# design.net
KiCad netlist of a schematic drawn in Altium Designer
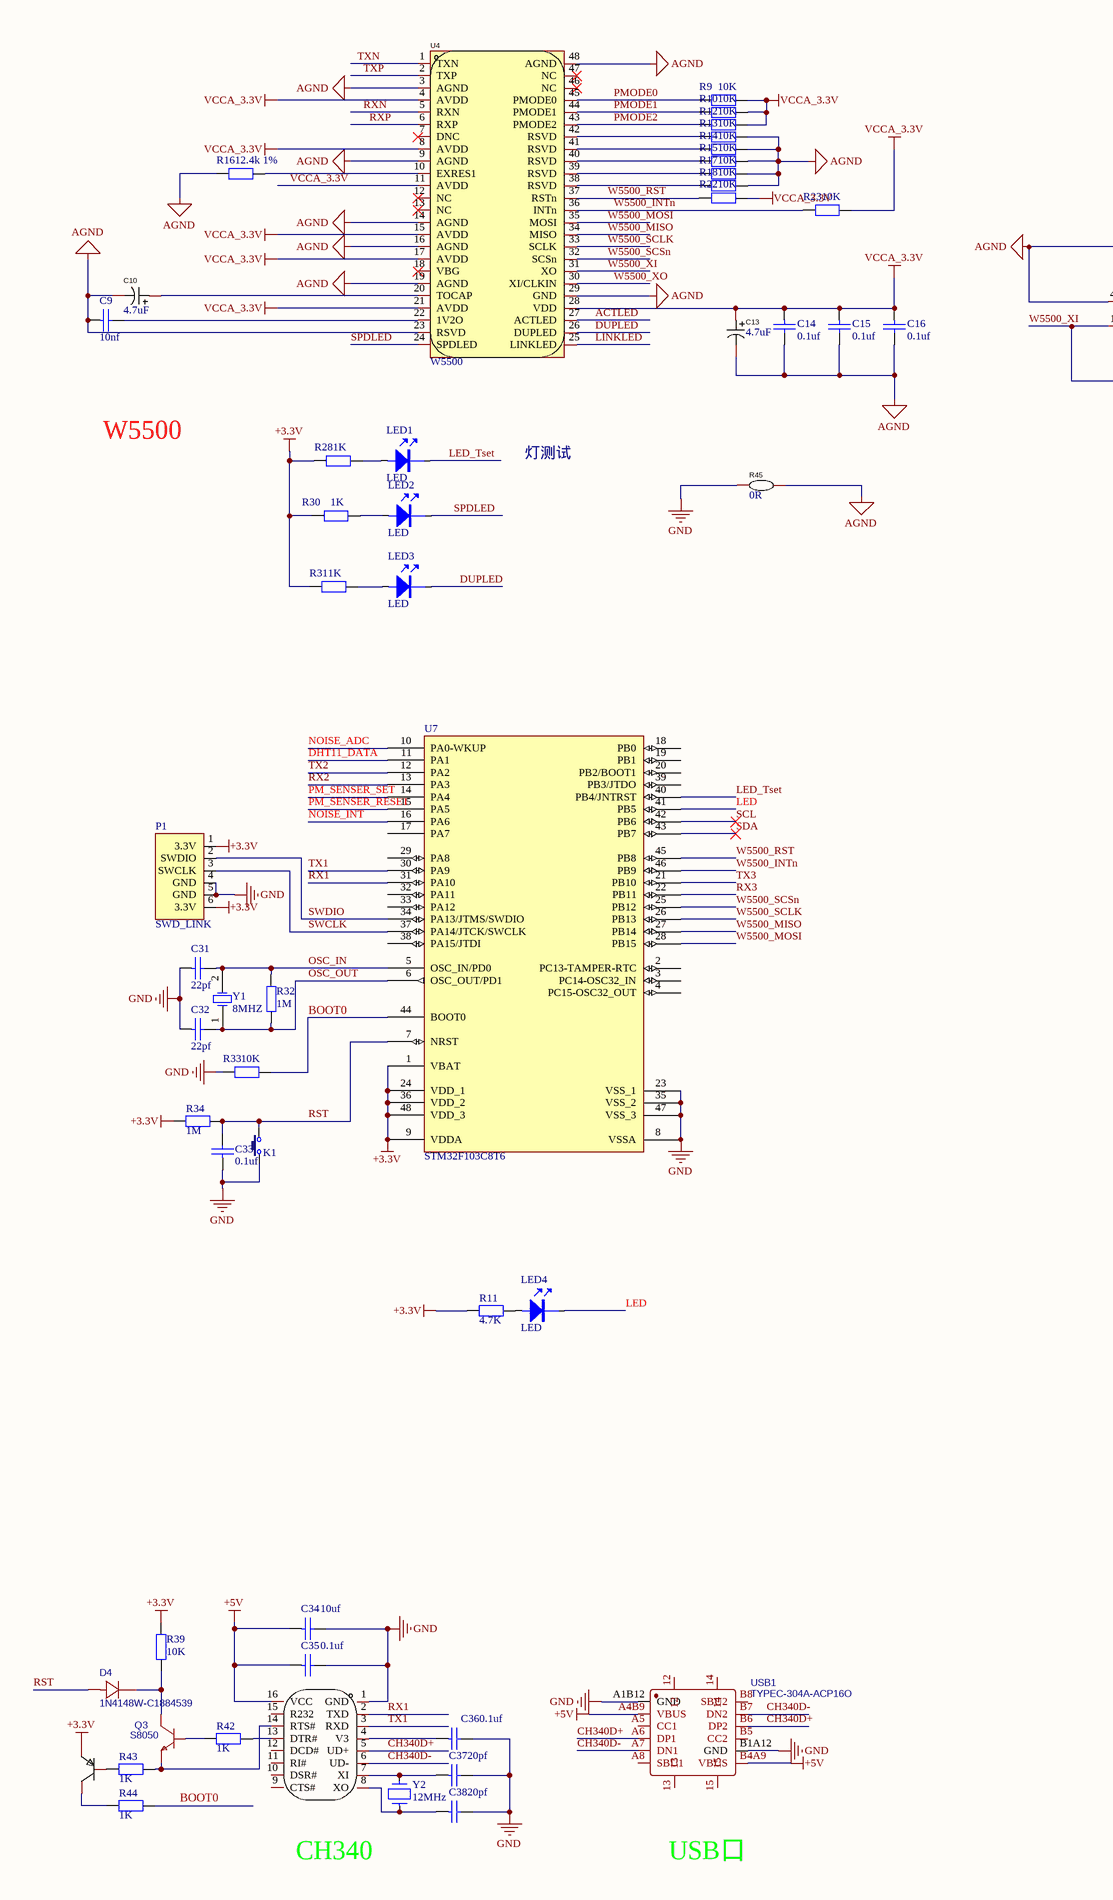
[diagram p0: 气象传感器.SchDoc, left]
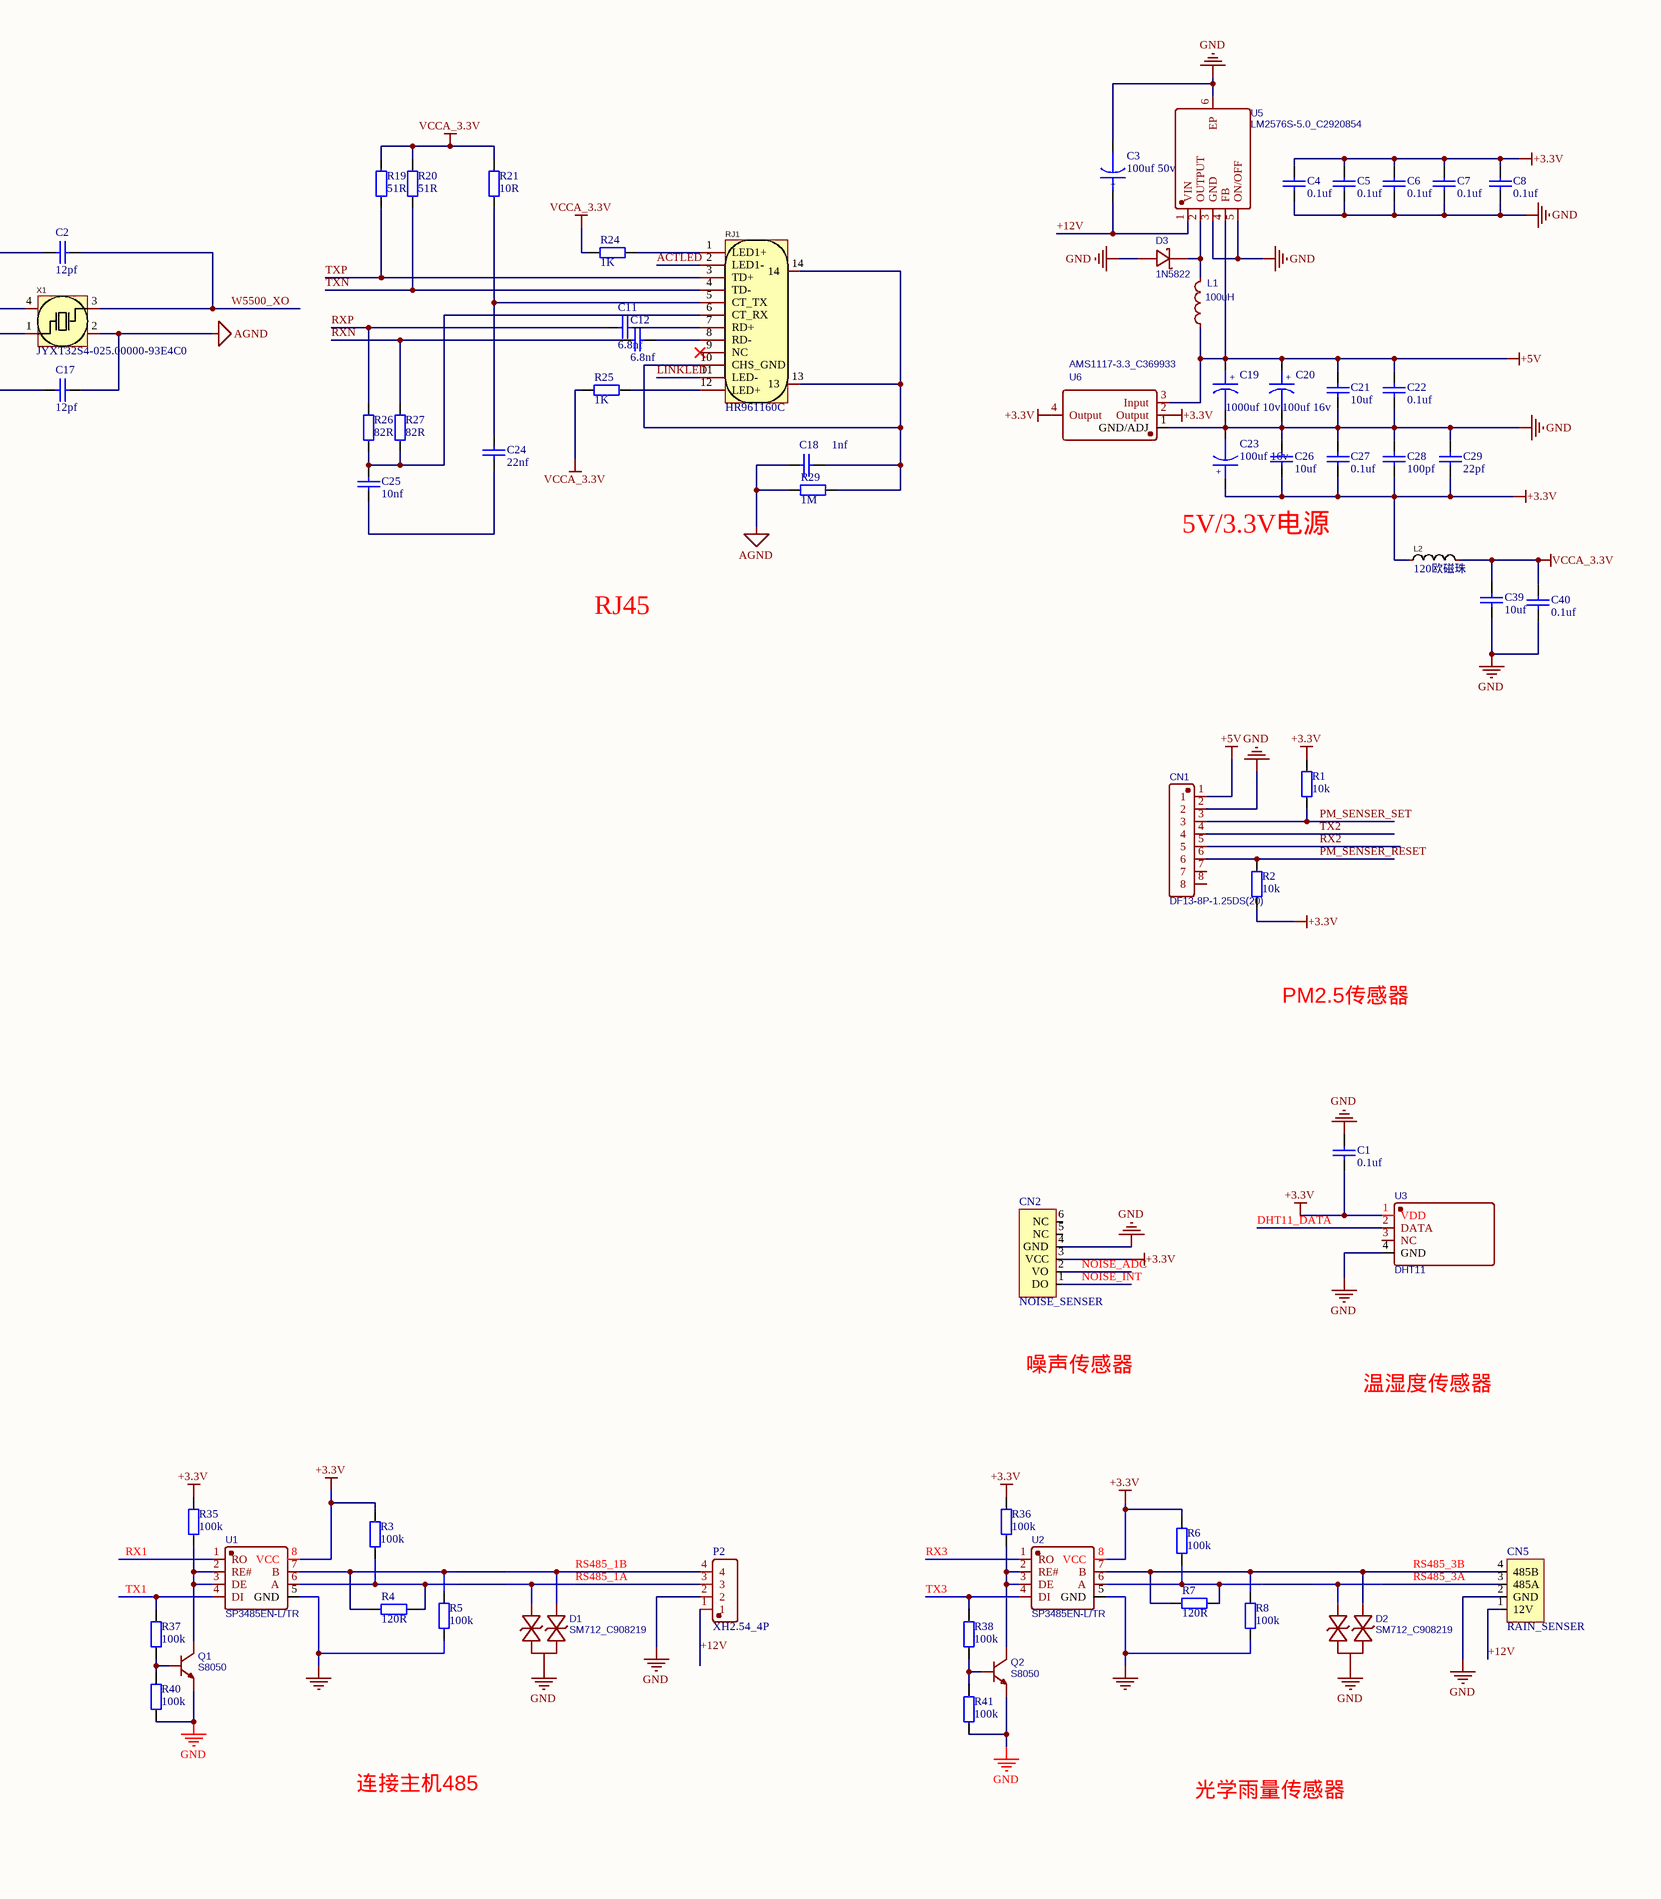
[diagram p1: 气象传感器.SchDoc, right]

(export (version "E")
  (design (tool "Eeschema 10.0.6"))
  (components
    (comp (ref "C1")
      (value "0.1uf")
      (footprint "0603C")
      (description "Capacitor")
      (libsource (lib "单灯控制器nanosim") (part "CAP"))
    )
    (comp (ref "C2")
      (value "12pf")
      (footprint "0603C")
      (description "Capacitor")
      (libsource (lib "GFZJ 主控制板") (part "CAP"))
    )
    (comp (ref "C3")
      (value "100uf 50v")
      (footprint "CAP-TH_BD8.0-P3.50-D0.6-FD")
      (description "Capacitor")
      (libsource (lib "GFZJ 主控制板") (part "CAP+"))
    )
    (comp (ref "C4")
      (value "0.1uf")
      (footprint "0603C")
      (description "Capacitor")
      (libsource (lib "GFZJ 主控制板") (part "CAP"))
    )
    (comp (ref "C5")
      (value "0.1uf")
      (footprint "0603C")
      (description "Capacitor")
      (libsource (lib "GFZJ 主控制板") (part "CAP"))
    )
    (comp (ref "C6")
      (value "0.1uf")
      (footprint "0603C")
      (description "Capacitor")
      (libsource (lib "GFZJ 主控制板") (part "CAP"))
    )
    (comp (ref "C7")
      (value "0.1uf")
      (footprint "0603C")
      (description "Capacitor")
      (libsource (lib "GFZJ 主控制板") (part "CAP"))
    )
    (comp (ref "C8")
      (value "0.1uf")
      (footprint "0603C")
      (description "Capacitor")
      (libsource (lib "GFZJ 主控制板") (part "CAP"))
    )
    (comp (ref "C9")
      (value "10nf")
      (footprint "0603C")
      (description "Capacitor")
      (libsource (lib "GFZJ 主控制板") (part "CAP"))
    )
    (comp (ref "C10")
      (value "4.7uF")
      (footprint "CAP-SMD_L1.6-W0.9-FD")
      (description "钽电容")
      (fields (field (name "MANUFACTURER") "Kyocera AVX") (field (name "MANUFACTURER PART") "F980J106MMA"))
      (libsource (lib "Modbus") (part "F980J106MMA"))
    )
    (comp (ref "C11")
      (value "6.8nf")
      (footprint "0603C")
      (description "Capacitor")
      (libsource (lib "GFZJ 主控制板") (part "CAP"))
    )
    (comp (ref "C12")
      (value "6.8nf")
      (footprint "0603C")
      (description "Capacitor")
      (libsource (lib "GFZJ 主控制板") (part "CAP"))
    )
    (comp (ref "C13")
      (value "4.7uF")
      (footprint "CAP-SMD_L1.6-W0.9-FD")
      (description "钽电容")
      (fields (field (name "MANUFACTURER") "Kyocera AVX") (field (name "MANUFACTURER PART") "F980J106MMA"))
      (libsource (lib "Modbus") (part "F980J106MMA"))
    )
    (comp (ref "C14")
      (value "0.1uf")
      (footprint "0603C")
      (description "Capacitor")
      (libsource (lib "GFZJ 主控制板") (part "CAP"))
    )
    (comp (ref "C15")
      (value "0.1uf")
      (footprint "0603C")
      (description "Capacitor")
      (libsource (lib "GFZJ 主控制板") (part "CAP"))
    )
    (comp (ref "C16")
      (value "0.1uf")
      (footprint "0603C")
      (description "Capacitor")
      (libsource (lib "GFZJ 主控制板") (part "CAP"))
    )
    (comp (ref "C17")
      (value "12pf")
      (footprint "0603C")
      (description "Capacitor")
      (libsource (lib "GFZJ 主控制板") (part "CAP"))
    )
    (comp (ref "C18")
      (value "1nf")
      (footprint "0603C")
      (description "Capacitor")
      (libsource (lib "GFZJ 主控制板") (part "CAP"))
    )
    (comp (ref "C19")
      (value "1000uf 10v")
      (footprint "CAP-TH_BD8.0-P3.50-D0.6-FD")
      (description "Capacitor")
      (libsource (lib "") (part "CAP+_1"))
    )
    (comp (ref "C20")
      (value "100uf 16v")
      (footprint "CAP-TH_BD5.0-P2.00-D0.8-FD")
      (description "Capacitor")
      (libsource (lib "") (part "CAP+_1"))
    )
    (comp (ref "C21")
      (value "10uf")
      (footprint "0805C")
      (description "Capacitor")
      (libsource (lib "GFZJ 主控制板") (part "CAP"))
    )
    (comp (ref "C22")
      (value "0.1uf")
      (footprint "0603C")
      (description "Capacitor")
      (libsource (lib "GFZJ 主控制板") (part "CAP"))
    )
    (comp (ref "C23")
      (value "100uf 16v")
      (footprint "CAP-TH_BD5.0-P2.00-D0.8-FD")
      (description "Capacitor")
      (libsource (lib "") (part "CAP+_1"))
    )
    (comp (ref "C24")
      (value "22nf")
      (footprint "0603C")
      (description "Capacitor")
      (libsource (lib "GFZJ 主控制板") (part "CAP"))
    )
    (comp (ref "C25")
      (value "10nf")
      (footprint "0603C")
      (description "Capacitor")
      (libsource (lib "GFZJ 主控制板") (part "CAP"))
    )
    (comp (ref "C26")
      (value "10uf")
      (footprint "0805C")
      (description "Capacitor")
      (libsource (lib "GFZJ 主控制板") (part "CAP"))
    )
    (comp (ref "C27")
      (value "0.1uf")
      (footprint "0603C")
      (description "Capacitor")
      (libsource (lib "GFZJ 主控制板") (part "CAP"))
    )
    (comp (ref "C28")
      (value "100pf")
      (footprint "0603C")
      (description "Capacitor")
      (libsource (lib "GFZJ 主控制板") (part "CAP"))
    )
    (comp (ref "C29")
      (value "22pf")
      (footprint "0603C")
      (description "Capacitor")
      (libsource (lib "GFZJ 主控制板") (part "CAP"))
    )
    (comp (ref "C31")
      (value "22pf")
      (footprint "0603C")
      (description "Capacitor")
      (libsource (lib "TNBZLY") (part "CAP"))
    )
    (comp (ref "C32")
      (value "22pf")
      (footprint "0603C")
      (description "Capacitor")
      (libsource (lib "TNBZLY") (part "CAP"))
    )
    (comp (ref "C33")
      (value "0.1uf")
      (footprint "0603C")
      (description "Capacitor")
      (libsource (lib "TNBZLY") (part "CAP"))
    )
    (comp (ref "C34")
      (value "10uf")
      (footprint "0805C")
      (description "Capacitor")
      (libsource (lib "TNBZLY") (part "CAP"))
    )
    (comp (ref "C35")
      (value "0.1uf")
      (footprint "0603C")
      (description "Capacitor")
      (libsource (lib "TNBZLY") (part "CAP"))
    )
    (comp (ref "C36")
      (value "0.1uf")
      (footprint "0603C")
      (description "Capacitor")
      (libsource (lib "TNBZLY") (part "CAP"))
    )
    (comp (ref "C37")
      (value "20pf")
      (footprint "0603C")
      (description "Capacitor")
      (libsource (lib "TNBZLY") (part "CAP"))
    )
    (comp (ref "C38")
      (value "20pf")
      (footprint "0603C")
      (description "Capacitor")
      (libsource (lib "TNBZLY") (part "CAP"))
    )
    (comp (ref "C39")
      (value "10uf")
      (footprint "0805C")
      (description "Capacitor")
      (libsource (lib "GFZJ 主控制板") (part "CAP"))
    )
    (comp (ref "C40")
      (value "0.1uf")
      (footprint "0603C")
      (description "Capacitor")
      (libsource (lib "GFZJ 主控制板") (part "CAP"))
    )
    (comp (ref "CN1")
      (value "DF13-8P-1.25DS(20)")
      (footprint "CONN-TH_8P-P1.25_DF13-8P-1.25DS-20")
      (fields (field (name "BOM_SUPPLIER PART") "C597874") (field (name "CONTRIBUTOR") "LCSC"))
      (libsource (lib "气象传感器") (part "DF13-8P-1.25DS(20)"))
    )
    (comp (ref "CN2")
      (value "NOISE_SENSER")
      (footprint "NOISE_SENSER")
      (libsource (lib "气象传感器") (part "NOISE_SENSER"))
    )
    (comp (ref "CN5")
      (value "RAIN_SENSER")
      (footprint "RAIN_SENSER")
      (description "雨量传感器接口")
      (libsource (lib "气象传感器") (part "RAIN_SENSER"))
    )
    (comp (ref "D1")
      (value "SM712_C908219")
      (footprint "SOT-23-3_L2.9-W1.3-P1.90-LS2.4-BR")
      (fields
        (field (name "BOM_SUPPLIER PART") "C908219")
        (field (name "BOM_MANUFACTURER PART") "SM712")
        (field (name "CONTRIBUTOR") "LCSC")
      )
      (libsource (lib "GFZJ 主控制板") (part "SM712_C908219"))
    )
    (comp (ref "D2")
      (value "SM712_C908219")
      (footprint "SOT-23-3_L2.9-W1.3-P1.90-LS2.4-BR")
      (fields
        (field (name "BOM_SUPPLIER PART") "C908219")
        (field (name "BOM_MANUFACTURER PART") "SM712")
        (field (name "CONTRIBUTOR") "LCSC")
      )
      (libsource (lib "GFZJ 主控制板") (part "SM712_C908219"))
    )
    (comp (ref "D3")
      (value "1N5822")
      (footprint "SMA_L4.4-W2.8-LS5.4-RD")
      (fields
        (field (name "BOM_SUPPLIER PART") "C437199")
        (field (name "BOM_MANUFACTURER PART") "1N5819")
        (field (name "CONTRIBUTOR") "LCSC")
      )
      (libsource (lib "TNBZLY") (part "1N5822"))
    )
    (comp (ref "D4")
      (value "1N4148W-C1884539")
      (footprint "SOD-123_4148")
      (fields
        (field (name "BOM_SUPPLIER PART") "C1884539")
        (field (name "BOM_MANUFACTURER PART") "1N4148W")
        (field (name "CONTRIBUTOR") "LCSC")
      )
      (libsource (lib "TNBZLY") (part "1N4148W-C1884539"))
    )
    (comp (ref "K1")
      (value "3x6x5")
      (footprint "TSW SMD-3*6*2.5")
      (description "3x6轻触开关")
      (fields (field (name "版权归属") "源创客"))
      (libsource (lib "TNBZLY") (part "TSW 3x6"))
    )
    (comp (ref "L1")
      (value "100uH")
      (footprint "IND-TH_BD10.0-P5.00-D0.7")
      (description "Inductance")
      (fields
        (field (name "BOM_MANUFACTURER PART") "VLU0810-101K")
        (field (name "BOM_SUPPLIER PART") "C72630")
      )
      (libsource (lib "TNBZLY") (part "L"))
    )
    (comp (ref "L2")
      (value "120欧磁珠")
      (footprint "L0603")
      (description "磁珠")
      (fields (field (name "MANUFACTURER") "Sunlord(顺络)") (field (name "MANUFACTURER PART") "GZ1608D121TF"))
      (libsource (lib "Modbus") (part "GZ1608D121TF"))
    )
    (comp (ref "LED1") (value "LED") (footprint "0603-LED") (libsource (lib "TNBZLY") (part "LED")))
    (comp (ref "LED2") (value "LED") (footprint "0603-LED") (libsource (lib "TNBZLY") (part "LED")))
    (comp (ref "LED3") (value "LED") (footprint "0603-LED") (libsource (lib "TNBZLY") (part "LED")))
    (comp (ref "LED4") (value "LED") (footprint "0603-LED") (libsource (lib "TNBZLY") (part "LED")))
    (comp (ref "P1") (value "SWD_LINK") (footprint "SWD_LINK") (libsource (lib "TNBZLY") (part "SWD_LINK")))
    (comp (ref "P2")
      (value "XH2.54_4P")
      (footprint "5.08 LINKER 1*4")
      (libsource (lib "GFZJ 整版") (part "XH2.54_4P"))
    )
    (comp (ref "Q1")
      (value "S8050")
      (footprint "SOT-23")
      (fields (field (name "BOM_SUPPLIER PART") "C266592") (field (name "CONTRIBUTOR") "mengruisheng"))
      (libsource (lib "altium-import") (part "root_2_mirrored_S8050_"))
    )
    (comp (ref "Q2")
      (value "S8050")
      (footprint "SOT-23")
      (fields (field (name "BOM_SUPPLIER PART") "C266592") (field (name "CONTRIBUTOR") "mengruisheng"))
      (libsource (lib "altium-import") (part "root_2_mirrored_S8050_"))
    )
    (comp (ref "Q3")
      (value "S8050")
      (footprint "SOT-23")
      (fields (field (name "BOM_SUPPLIER PART") "C266592") (field (name "CONTRIBUTOR") "mengruisheng"))
      (libsource (lib "altium-import") (part "root_2_S8050_"))
    )
    (comp (ref "Q4")
      (value "S8550")
      (footprint "SOT-23-3_L2.9-W1.3-P1.90-LS2.4-BR")
      (fields (field (name "MANUFACTURER") "UMW(友台半导体)"))
      (libsource (lib "TNBZLY") (part "S8550"))
    )
    (comp (ref "R1")
      (value "10k")
      (footprint "0603R")
      (description "Resistor SMD - IEC symbol version")
      (fields (field (name "Comment") "Resistor"))
      (libsource (lib "") (part "RES_1"))
    )
    (comp (ref "R2")
      (value "10k")
      (footprint "0603R")
      (description "Resistor SMD - IEC symbol version")
      (fields (field (name "Comment") "Resistor"))
      (libsource (lib "") (part "RES_1"))
    )
    (comp (ref "R3")
      (value "100k")
      (footprint "0603R")
      (description "Resistor SMD - IEC symbol version")
      (fields (field (name "Comment") "Resistor"))
      (libsource (lib "GFZJ 电源板") (part "RES"))
    )
    (comp (ref "R4")
      (value "120R")
      (footprint "0603R")
      (description "Resistor SMD - IEC symbol version")
      (fields (field (name "Comment") "Resistor"))
      (libsource (lib "") (part "RES_3"))
    )
    (comp (ref "R5")
      (value "100k")
      (footprint "0603R")
      (description "Resistor SMD - IEC symbol version")
      (fields (field (name "Comment") "Resistor"))
      (libsource (lib "") (part "RES_1"))
    )
    (comp (ref "R6")
      (value "100k")
      (footprint "0603R")
      (description "Resistor SMD - IEC symbol version")
      (fields (field (name "Comment") "Resistor"))
      (libsource (lib "") (part "RES_1"))
    )
    (comp (ref "R7")
      (value "120R")
      (footprint "0603R")
      (description "Resistor SMD - IEC symbol version")
      (fields (field (name "Comment") "Resistor"))
      (libsource (lib "") (part "RES_2"))
    )
    (comp (ref "R8")
      (value "100k")
      (footprint "0603R")
      (description "Resistor SMD - IEC symbol version")
      (fields (field (name "Comment") "Resistor"))
      (libsource (lib "") (part "RES_1"))
    )
    (comp (ref "R9")
      (value "10K")
      (footprint "0603R")
      (description "Resistor SMD - IEC symbol version")
      (fields (field (name "Comment") "Resistor"))
      (libsource (lib "TNBZLY") (part "RES"))
    )
    (comp (ref "R10")
      (value "10K")
      (footprint "0603R")
      (description "Resistor SMD - IEC symbol version")
      (fields (field (name "Comment") "Resistor"))
      (libsource (lib "TNBZLY") (part "RES"))
    )
    (comp (ref "R11")
      (value "4.7K")
      (footprint "0603R")
      (description "Resistor SMD - IEC symbol version")
      (fields (field (name "Comment") "Resistor"))
      (libsource (lib "") (part "RES_2"))
    )
    (comp (ref "R12")
      (value "10K")
      (footprint "0603R")
      (description "Resistor SMD - IEC symbol version")
      (fields (field (name "Comment") "Resistor"))
      (libsource (lib "TNBZLY") (part "RES"))
    )
    (comp (ref "R13")
      (value "10K")
      (footprint "0603R")
      (description "Resistor SMD - IEC symbol version")
      (fields (field (name "Comment") "Resistor"))
      (libsource (lib "TNBZLY") (part "RES"))
    )
    (comp (ref "R14")
      (value "10K")
      (footprint "0603R")
      (description "Resistor SMD - IEC symbol version")
      (fields (field (name "Comment") "Resistor"))
      (libsource (lib "TNBZLY") (part "RES"))
    )
    (comp (ref "R15")
      (value "10K")
      (footprint "0603R")
      (description "Resistor SMD - IEC symbol version")
      (fields (field (name "Comment") "Resistor"))
      (libsource (lib "TNBZLY") (part "RES"))
    )
    (comp (ref "R16")
      (value "12.4k 1%")
      (footprint "0603R")
      (description "Resistor SMD - IEC symbol version")
      (fields (field (name "Comment") "Resistor"))
      (libsource (lib "TNBZLY") (part "RES"))
    )
    (comp (ref "R17")
      (value "10K")
      (footprint "0603R")
      (description "Resistor SMD - IEC symbol version")
      (fields (field (name "Comment") "Resistor"))
      (libsource (lib "TNBZLY") (part "RES"))
    )
    (comp (ref "R18")
      (value "10K")
      (footprint "0603R")
      (description "Resistor SMD - IEC symbol version")
      (fields (field (name "Comment") "Resistor"))
      (libsource (lib "TNBZLY") (part "RES"))
    )
    (comp (ref "R19")
      (value "51R")
      (footprint "0603R")
      (description "Resistor SMD - IEC symbol version")
      (fields (field (name "Comment") "Resistor"))
      (libsource (lib "") (part "RES_2"))
    )
    (comp (ref "R20")
      (value "51R")
      (footprint "0603R")
      (description "Resistor SMD - IEC symbol version")
      (fields (field (name "Comment") "Resistor"))
      (libsource (lib "") (part "RES_2"))
    )
    (comp (ref "R21")
      (value "10R")
      (footprint "0603R")
      (description "Resistor SMD - IEC symbol version")
      (fields (field (name "Comment") "Resistor"))
      (libsource (lib "") (part "RES_2"))
    )
    (comp (ref "R22")
      (value "10K")
      (footprint "0603R")
      (description "Resistor SMD - IEC symbol version")
      (fields (field (name "Comment") "Resistor"))
      (libsource (lib "TNBZLY") (part "RES"))
    )
    (comp (ref "R23")
      (value "10K")
      (footprint "0603R")
      (description "Resistor SMD - IEC symbol version")
      (fields (field (name "Comment") "Resistor"))
      (libsource (lib "TNBZLY") (part "RES"))
    )
    (comp (ref "R24")
      (value "1K")
      (footprint "0603R")
      (description "Resistor SMD - IEC symbol version")
      (fields (field (name "Comment") "Resistor"))
      (libsource (lib "") (part "RES_1"))
    )
    (comp (ref "R25")
      (value "1K")
      (footprint "0603R")
      (description "Resistor SMD - IEC symbol version")
      (fields (field (name "Comment") "Resistor"))
      (libsource (lib "") (part "RES_1"))
    )
    (comp (ref "R26")
      (value "82R")
      (footprint "0603R")
      (description "Resistor SMD - IEC symbol version")
      (fields (field (name "Comment") "Resistor"))
      (libsource (lib "") (part "RES_2"))
    )
    (comp (ref "R27")
      (value "82R")
      (footprint "0603R")
      (description "Resistor SMD - IEC symbol version")
      (fields (field (name "Comment") "Resistor"))
      (libsource (lib "") (part "RES_2"))
    )
    (comp (ref "R28")
      (value "1K")
      (footprint "0603R")
      (description "Resistor SMD - IEC symbol version")
      (fields (field (name "Comment") "Resistor"))
      (libsource (lib "TNBZLY") (part "RES"))
    )
    (comp (ref "R29")
      (value "1M")
      (footprint "0603R")
      (description "Resistor SMD - IEC symbol version")
      (fields (field (name "Comment") "Resistor"))
      (libsource (lib "") (part "RES_1"))
    )
    (comp (ref "R30")
      (value "1K")
      (footprint "0603R")
      (description "Resistor SMD - IEC symbol version")
      (fields (field (name "Comment") "Resistor"))
      (libsource (lib "TNBZLY") (part "RES"))
    )
    (comp (ref "R31")
      (value "1K")
      (footprint "0603R")
      (description "Resistor SMD - IEC symbol version")
      (fields (field (name "Comment") "Resistor"))
      (libsource (lib "TNBZLY") (part "RES"))
    )
    (comp (ref "R32")
      (value "1M")
      (footprint "0603R")
      (description "Resistor SMD - IEC symbol version")
      (fields (field (name "Comment") "Resistor"))
      (libsource (lib "") (part "RES_3"))
    )
    (comp (ref "R33")
      (value "10K")
      (footprint "0603R")
      (description "Resistor SMD - IEC symbol version")
      (fields (field (name "Comment") "Resistor"))
      (libsource (lib "TNBZLY") (part "RES"))
    )
    (comp (ref "R34")
      (value "1M")
      (footprint "0603R")
      (description "Resistor SMD - IEC symbol version")
      (fields (field (name "Comment") "Resistor"))
      (libsource (lib "TNBZLY") (part "RES"))
    )
    (comp (ref "R35")
      (value "100k")
      (footprint "0603R")
      (description "Resistor SMD - IEC symbol version")
      (fields (field (name "Comment") "Resistor"))
      (libsource (lib "GFZJ 电源板") (part "RES"))
    )
    (comp (ref "R36")
      (value "100k")
      (footprint "0603R")
      (description "Resistor SMD - IEC symbol version")
      (fields (field (name "Comment") "Resistor"))
      (libsource (lib "GFZJ 电源板") (part "RES"))
    )
    (comp (ref "R37")
      (value "100k")
      (footprint "0603R")
      (description "Resistor SMD - IEC symbol version")
      (fields (field (name "Comment") "Resistor"))
      (libsource (lib "GFZJ 电源板") (part "RES"))
    )
    (comp (ref "R38")
      (value "100k")
      (footprint "0603R")
      (description "Resistor SMD - IEC symbol version")
      (fields (field (name "Comment") "Resistor"))
      (libsource (lib "GFZJ 电源板") (part "RES"))
    )
    (comp (ref "R39")
      (value "10K")
      (footprint "0603R")
      (description "Resistor SMD - IEC symbol version")
      (fields (field (name "Comment") "Resistor"))
      (libsource (lib "") (part "RES_2"))
    )
    (comp (ref "R40")
      (value "100k")
      (footprint "0603R")
      (description "Resistor SMD - IEC symbol version")
      (fields (field (name "Comment") "Resistor"))
      (libsource (lib "GFZJ 电源板") (part "RES"))
    )
    (comp (ref "R41")
      (value "100k")
      (footprint "0603R")
      (description "Resistor SMD - IEC symbol version")
      (fields (field (name "Comment") "Resistor"))
      (libsource (lib "GFZJ 电源板") (part "RES"))
    )
    (comp (ref "R42")
      (value "1K")
      (footprint "0603R")
      (description "Resistor SMD - IEC symbol version")
      (fields (field (name "Comment") "Resistor"))
      (libsource (lib "TNBZLY") (part "RES"))
    )
    (comp (ref "R43")
      (value "1K")
      (footprint "0603R")
      (description "Resistor SMD - IEC symbol version")
      (fields (field (name "Comment") "Resistor"))
      (libsource (lib "TNBZLY") (part "RES"))
    )
    (comp (ref "R44")
      (value "1K")
      (footprint "0603R")
      (description "Resistor SMD - IEC symbol version")
      (fields (field (name "Comment") "Resistor"))
      (libsource (lib "TNBZLY") (part "RES"))
    )
    (comp (ref "R45")
      (value "0R")
      (footprint "R0603")
      (description "电阻")
      (fields
        (field (name "MANUFACTURER") "UNI-ROYAL(厚声)")
        (field (name "MANUFACTURER PART") "TC0325B330JT5E")
      )
      (libsource (lib "Modbus") (part "TC0325B330JT5E"))
    )
    (comp (ref "RJ1")
      (value "HR961160C")
      (footprint "RJ45-SMD_HR961160C")
      (description "RJ45")
      (fields (field (name "MANUFACTURER") "HANRUN(汉仁)"))
      (libsource (lib "Modbus") (part "HR961160C"))
    )
    (comp (ref "U1")
      (value "SP3485EN-L/TR")
      (footprint "SOIC-8_L5.0-W4.0-P1.27-LS6.0-BL")
      (fields (field (name "BOM_SUPPLIER PART") "C8963"))
      (libsource (lib "GFZJ 主控制板") (part "SP3485EN-L/TR"))
    )
    (comp (ref "U2")
      (value "SP3485EN-L/TR")
      (footprint "SOIC-8_L5.0-W4.0-P1.27-LS6.0-BL")
      (fields (field (name "BOM_SUPPLIER PART") "C8963"))
      (libsource (lib "GFZJ 主控制板") (part "SP3485EN-L/TR"))
    )
    (comp (ref "U3")
      (value "DHT11")
      (footprint "DHT11")
      (fields (field (name "BOM_SUPPLIER PART") "C117051") (field (name "CONTRIBUTOR") "LCSC"))
      (libsource (lib "气象传感器") (part "DHT11"))
    )
    (comp (ref "U4")
      (value "W5500")
      (footprint "LQFP-48_L7.0-W7.0-P0.50-LS9.0-BL")
      (description "以太网控制芯片")
      (fields (field (name "MANUFACTURER") "WIZNET"))
      (libsource (lib "Modbus") (part "W5500"))
    )
    (comp (ref "U5")
      (value "LM2576S-5.0_C2920854")
      (footprint "TO-263-5_L10.2-W8.6-P1.70-LS14.4-TL")
      (description "LM2576S-5.0")
      (fields (field (name "BOM_SUPPLIER PART") "C2920854") (field (name "CONTRIBUTOR") "LCSC"))
      (libsource (lib "TNBZLY") (part "LM2576S-5.0_C2920854"))
    )
    (comp (ref "U6")
      (value "AMS1117-3.3_C369933")
      (footprint "SOT-223-4_L6.5-W3.5-P2.30-LS7.0-BR")
      (description "AMS1117-3.3")
      (fields (field (name "BOM_SUPPLIER PART") "C369933") (field (name "CONTRIBUTOR") "LCSC"))
      (libsource (lib "GFZJ 主控制板") (part "AMS1117-3.3_C369933"))
    )
    (comp (ref "U7")
      (value "STM32F103C8T6")
      (footprint "LQFP48 7X7_M")
      (description "Flaah:64/RAM:20/IO:36")
      (fields (field (name "版权归属") "源创客"))
      (libsource (lib "TNBZLY") (part "STM32F103C8T6"))
    )
    (comp (ref "U8")
      (value "CH340G")
      (footprint "SOIC-16_L9.9-W3.9-P1.27-LS6.0-BL")
      (fields (field (name "MANUFACTURER") "WCH(南京沁恒)"))
      (libsource (lib "TNBZLY") (part "CH340G"))
    )
    (comp (ref "USB1")
      (value "TYPEC-304A-ACP16O")
      (footprint "USB-SMD_TYPEC-304A-ACP16O")
      (fields (field (name "BOM_SUPPLIER PART") "C2909610") (field (name "CONTRIBUTOR") "LCSC"))
      (libsource (lib "TNBZLY") (part "TYPEC-304A-ACP16O"))
    )
    (comp (ref "X1")
      (value "JYXT32S4-025.00000-93E4C0")
      (footprint "OSC-SMD_4P-L3.2-W2.5-BL")
      (description "25Mhz晶振")
      (fields (field (name "MANUFACTURER") "JINGYOU(晶优)"))
      (libsource (lib "Modbus") (part "JYXT32S4-025.00000-93E4C0"))
    )
    (comp (ref "Y1")
      (value "8MHZ")
      (footprint "XTAL1")
      (description "Crystal Oscillator")
      (fields (field (name "PUBLISHER") "Altium Limited"))
      (libsource (lib "TNBZLY") (part "XTAL"))
    )
    (comp (ref "Y2")
      (value "12MHz")
      (footprint "XTAL1")
      (description "Crystal Oscillator")
      (libsource (lib "LXKJSJ") (part "XTAL"))
    )
  )
  (nets
    (net (code "1") (name "+3.3V") (class "Default")
      (node (ref "C1") (pin "1") (pinfunction "1_1") (pintype "passive"))
      (node (ref "C23") (pin "1") (pinfunction "1_1") (pintype "passive"))
      (node (ref "C26") (pin "2") (pinfunction "2_2") (pintype "passive"))
      (node (ref "C27") (pin "2") (pinfunction "2_2") (pintype "passive"))
      (node (ref "C28") (pin "2") (pinfunction "2_2") (pintype "passive"))
      (node (ref "C29") (pin "2") (pinfunction "2_2") (pintype "passive"))
      (node (ref "C4") (pin "1") (pinfunction "1_1") (pintype "passive"))
      (node (ref "C5") (pin "1") (pinfunction "1_1") (pintype "passive"))
      (node (ref "C6") (pin "1") (pinfunction "1_1") (pintype "passive"))
      (node (ref "C7") (pin "1") (pinfunction "1_1") (pintype "passive"))
      (node (ref "C8") (pin "1") (pinfunction "1_1") (pintype "passive"))
      (node (ref "CN2") (pin "3") (pinfunction "VCC_3") (pintype "passive"))
      (node (ref "L2") (pin "1") (pinfunction "1_1") (pintype "passive"))
      (node (ref "P1") (pin "1") (pinfunction "3.3V_1") (pintype "passive"))
      (node (ref "P1") (pin "6") (pinfunction "3.3V_6") (pintype "passive"))
      (node (ref "Q4") (pin "2") (pinfunction "E_2") (pintype "passive"))
      (node (ref "R1") (pin "2") (pinfunction "2_2") (pintype "passive"))
      (node (ref "R11") (pin "2") (pinfunction "2_2") (pintype "passive"))
      (node (ref "R2") (pin "1") (pinfunction "1_1") (pintype "passive"))
      (node (ref "R28") (pin "2") (pinfunction "2_2") (pintype "passive"))
      (node (ref "R3") (pin "1") (pinfunction "1_1") (pintype "passive"))
      (node (ref "R30") (pin "2") (pinfunction "2_2") (pintype "passive"))
      (node (ref "R31") (pin "2") (pinfunction "2_2") (pintype "passive"))
      (node (ref "R34") (pin "2") (pinfunction "2_2") (pintype "passive"))
      (node (ref "R35") (pin "1") (pinfunction "1_1") (pintype "passive"))
      (node (ref "R36") (pin "1") (pinfunction "1_1") (pintype "passive"))
      (node (ref "R39") (pin "1") (pinfunction "1_1") (pintype "passive"))
      (node (ref "R6") (pin "2") (pinfunction "2_2") (pintype "passive"))
      (node (ref "U1") (pin "8") (pinfunction "VCC_8") (pintype "passive"))
      (node (ref "U2") (pin "8") (pinfunction "VCC_8") (pintype "passive"))
      (node (ref "U3") (pin "1") (pinfunction "VDD_1") (pintype "passive"))
      (node (ref "U6") (pin "2") (pinfunction "Output_2") (pintype "passive"))
      (node (ref "U6") (pin "4") (pinfunction "Output_4") (pintype "passive"))
      (node (ref "U7") (pin "1") (pinfunction "VBAT_1") (pintype "power_in"))
      (node (ref "U7") (pin "24") (pinfunction "VDD_1_24") (pintype "power_in"))
      (node (ref "U7") (pin "36") (pinfunction "VDD_2_36") (pintype "power_in"))
      (node (ref "U7") (pin "48") (pinfunction "VDD_3_48") (pintype "power_in"))
      (node (ref "U7") (pin "9") (pinfunction "VDDA_9") (pintype "power_in"))
    )
    (net (code "2") (name "+5V") (class "Default")
      (node (ref "C19") (pin "1") (pinfunction "1_1") (pintype "passive"))
      (node (ref "C20") (pin "1") (pinfunction "1_1") (pintype "passive"))
      (node (ref "C21") (pin "1") (pinfunction "1_1") (pintype "passive"))
      (node (ref "C22") (pin "1") (pinfunction "1_1") (pintype "passive"))
      (node (ref "C34") (pin "1") (pinfunction "1_1") (pintype "passive"))
      (node (ref "C35") (pin "1") (pinfunction "1_1") (pintype "passive"))
      (node (ref "CN1") (pin "1") (pinfunction "1_1") (pintype "passive"))
      (node (ref "L1") (pin "1") (pinfunction "1_1") (pintype "passive"))
      (node (ref "U5") (pin "4") (pinfunction "FB_4") (pintype "passive"))
      (node (ref "U6") (pin "3") (pinfunction "Input_3") (pintype "passive"))
      (node (ref "U8") (pin "16") (pinfunction "VCC_16") (pintype "passive"))
      (node (ref "USB1") (pin "A4B9") (pinfunction "VBUS_A4B9") (pintype "passive"))
      (node (ref "USB1") (pin "B4A9") (pinfunction "VBUS_B4A9") (pintype "passive"))
    )
    (net (code "3") (name "/+12V") (class "Default")
      (node (ref "C3") (pin "1") (pinfunction "1_1") (pintype "passive"))
      (node (ref "CN5") (pin "1") (pinfunction "12V_1") (pintype "passive"))
      (node (ref "P2") (pin "1") (pinfunction "1_1") (pintype "passive"))
      (node (ref "U5") (pin "1") (pinfunction "VIN_1") (pintype "passive"))
    )
    (net (code "4") (name "/ACTLED") (class "Default")
      (node (ref "RJ1") (pin "2") (pinfunction "LED1-_2") (pintype "passive"))
      (node (ref "U4") (pin "27") (pinfunction "ACTLED_27") (pintype "passive"))
    )
    (net (code "5") (name "/BOOT0") (class "Default")
      (node (ref "R33") (pin "1") (pinfunction "1_1") (pintype "passive"))
      (node (ref "R44") (pin "1") (pinfunction "1_1") (pintype "passive"))
      (node (ref "U7") (pin "44") (pinfunction "BOOT0_44") (pintype "passive"))
    )
    (net (code "6") (name "/CH340D+") (class "Default")
      (node (ref "U8") (pin "5") (pinfunction "UD+_5") (pintype "passive"))
      (node (ref "USB1") (pin "A6") (pinfunction "DP1_A6") (pintype "passive"))
      (node (ref "USB1") (pin "B6") (pinfunction "DP2_B6") (pintype "passive"))
    )
    (net (code "7") (name "/CH340D-") (class "Default")
      (node (ref "U8") (pin "6") (pinfunction "UD-_6") (pintype "passive"))
      (node (ref "USB1") (pin "A7") (pinfunction "DN1_A7") (pintype "passive"))
      (node (ref "USB1") (pin "B7") (pinfunction "DN2_B7") (pintype "passive"))
    )
    (net (code "8") (name "/DHT11_DATA") (class "Default")
      (node (ref "U3") (pin "2") (pinfunction "DATA_2") (pintype "passive"))
      (node (ref "U7") (pin "11") (pinfunction "PA1_11") (pintype "passive"))
    )
    (net (code "9") (name "/DUPLED") (class "Default")
      (node (ref "LED3") (pin "2") (pinfunction "2_2") (pintype "passive"))
      (node (ref "U4") (pin "26") (pinfunction "DUPLED_26") (pintype "passive"))
    )
    (net (code "10") (name "/LED") (class "Default")
      (node (ref "LED4") (pin "2") (pinfunction "2_2") (pintype "passive"))
      (node (ref "U7") (pin "41") (pinfunction "PB5_41") (pintype "bidirectional"))
    )
    (net (code "11") (name "/LED_Tset") (class "Default")
      (node (ref "LED1") (pin "2") (pinfunction "2_2") (pintype "passive"))
      (node (ref "U7") (pin "40") (pinfunction "PB4/JNTRST_40") (pintype "bidirectional"))
    )
    (net (code "12") (name "/LINKLED") (class "Default")
      (node (ref "RJ1") (pin "11") (pinfunction "LED-_11") (pintype "passive"))
      (node (ref "U4") (pin "25") (pinfunction "LINKLED_25") (pintype "passive"))
    )
    (net (code "13") (name "/NOISE_ADC") (class "Default")
      (node (ref "CN2") (pin "2") (pinfunction "VO_2") (pintype "passive"))
      (node (ref "U7") (pin "10") (pinfunction "PA0-WKUP_10") (pintype "passive"))
    )
    (net (code "14") (name "/NOISE_INT") (class "Default")
      (node (ref "CN2") (pin "1") (pinfunction "DO_1") (pintype "passive"))
      (node (ref "U7") (pin "16") (pinfunction "PA6_16") (pintype "passive"))
    )
    (net (code "15") (name "/OSC_IN") (class "Default")
      (node (ref "C31") (pin "2") (pinfunction "2_2") (pintype "passive"))
      (node (ref "R32") (pin "2") (pinfunction "2_2") (pintype "passive"))
      (node (ref "U7") (pin "5") (pinfunction "OSC_IN/PD0_5") (pintype "passive"))
      (node (ref "Y1") (pin "2") (pinfunction "OSC2_2") (pintype "passive"))
    )
    (net (code "16") (name "/OSC_OUT") (class "Default")
      (node (ref "C32") (pin "2") (pinfunction "2_2") (pintype "passive"))
      (node (ref "R32") (pin "1") (pinfunction "1_1") (pintype "passive"))
      (node (ref "U7") (pin "6") (pinfunction "OSC_OUT/PD1_6") (pintype "output"))
      (node (ref "Y1") (pin "1") (pinfunction "OSC1_1") (pintype "passive"))
    )
    (net (code "17") (name "/PMODE0") (class "Default")
      (node (ref "R9") (pin "2") (pinfunction "2_2") (pintype "passive"))
      (node (ref "U4") (pin "45") (pinfunction "PMODE0_45") (pintype "passive"))
    )
    (net (code "18") (name "/PMODE1") (class "Default")
      (node (ref "R10") (pin "2") (pinfunction "2_2") (pintype "passive"))
      (node (ref "U4") (pin "44") (pinfunction "PMODE1_44") (pintype "passive"))
    )
    (net (code "19") (name "/PMODE2") (class "Default")
      (node (ref "R12") (pin "2") (pinfunction "2_2") (pintype "passive"))
      (node (ref "U4") (pin "43") (pinfunction "PMODE2_43") (pintype "passive"))
    )
    (net (code "20") (name "/PM_SENSER_RESET") (class "Default")
      (node (ref "CN1") (pin "6") (pinfunction "6_6") (pintype "passive"))
      (node (ref "R2") (pin "2") (pinfunction "2_2") (pintype "passive"))
      (node (ref "U7") (pin "15") (pinfunction "PA5_15") (pintype "passive"))
    )
    (net (code "21") (name "/PM_SENSER_SET") (class "Default")
      (node (ref "CN1") (pin "3") (pinfunction "3_3") (pintype "passive"))
      (node (ref "R1") (pin "1") (pinfunction "1_1") (pintype "passive"))
      (node (ref "U7") (pin "14") (pinfunction "PA4_14") (pintype "passive"))
    )
    (net (code "22") (name "/RS485_1A") (class "Default")
      (node (ref "D1") (pin "2") (pinfunction "2_2") (pintype "passive"))
      (node (ref "P2") (pin "3") (pinfunction "3_3") (pintype "passive"))
      (node (ref "R3") (pin "2") (pinfunction "2_2") (pintype "passive"))
      (node (ref "R4") (pin "2") (pinfunction "2_2") (pintype "passive"))
      (node (ref "U1") (pin "6") (pinfunction "A_6") (pintype "passive"))
    )
    (net (code "23") (name "/RS485_1B") (class "Default")
      (node (ref "D1") (pin "1") (pinfunction "1_1") (pintype "passive"))
      (node (ref "P2") (pin "4") (pinfunction "4_4") (pintype "passive"))
      (node (ref "R4") (pin "1") (pinfunction "1_1") (pintype "passive"))
      (node (ref "R5") (pin "2") (pinfunction "2_2") (pintype "passive"))
      (node (ref "U1") (pin "7") (pinfunction "B_7") (pintype "passive"))
    )
    (net (code "24") (name "/RS485_3A") (class "Default")
      (node (ref "CN5") (pin "3") (pinfunction "485A_3") (pintype "passive"))
      (node (ref "D2") (pin "2") (pinfunction "2_2") (pintype "passive"))
      (node (ref "R6") (pin "1") (pinfunction "1_1") (pintype "passive"))
      (node (ref "R7") (pin "1") (pinfunction "1_1") (pintype "passive"))
      (node (ref "U2") (pin "6") (pinfunction "A_6") (pintype "passive"))
    )
    (net (code "25") (name "/RS485_3B") (class "Default")
      (node (ref "CN5") (pin "4") (pinfunction "485B_4") (pintype "passive"))
      (node (ref "D2") (pin "1") (pinfunction "1_1") (pintype "passive"))
      (node (ref "R7") (pin "2") (pinfunction "2_2") (pintype "passive"))
      (node (ref "R8") (pin "2") (pinfunction "2_2") (pintype "passive"))
      (node (ref "U2") (pin "7") (pinfunction "B_7") (pintype "passive"))
    )
    (net (code "26") (name "/RST") (class "Default")
      (node (ref "C33") (pin "2") (pinfunction "2_2") (pintype "passive"))
      (node (ref "D4") (pin "2") (pinfunction "2_2") (pintype "passive"))
      (node (ref "K1") (pin "2") (pinfunction "2_2") (pintype "passive"))
      (node (ref "R34") (pin "1") (pinfunction "1_1") (pintype "passive"))
      (node (ref "U7") (pin "7") (pinfunction "NRST_7") (pintype "bidirectional"))
    )
    (net (code "27") (name "/RX1") (class "Default")
      (node (ref "U1") (pin "1") (pinfunction "RO_1") (pintype "passive"))
      (node (ref "U7") (pin "31") (pinfunction "PA10_31") (pintype "bidirectional"))
      (node (ref "U8") (pin "2") (pinfunction "TXD_2") (pintype "passive"))
    )
    (net (code "28") (name "/RX2") (class "Default")
      (node (ref "CN1") (pin "5") (pinfunction "5_5") (pintype "passive"))
      (node (ref "U7") (pin "13") (pinfunction "PA3_13") (pintype "passive"))
    )
    (net (code "29") (name "/RX3") (class "Default")
      (node (ref "U2") (pin "1") (pinfunction "RO_1") (pintype "passive"))
      (node (ref "U7") (pin "22") (pinfunction "PB11_22") (pintype "bidirectional"))
    )
    (net (code "30") (name "/RXN") (class "Default")
      (node (ref "C12") (pin "1") (pinfunction "1_1") (pintype "passive"))
      (node (ref "R27") (pin "1") (pinfunction "1_1") (pintype "passive"))
      (node (ref "U4") (pin "5") (pinfunction "RXN_5") (pintype "passive"))
    )
    (net (code "31") (name "/RXP") (class "Default")
      (node (ref "C11") (pin "1") (pinfunction "1_1") (pintype "passive"))
      (node (ref "R26") (pin "1") (pinfunction "1_1") (pintype "passive"))
      (node (ref "U4") (pin "6") (pinfunction "RXP_6") (pintype "passive"))
    )
    (net (code "32") (name "/SCL") (class "Default")
      (node (ref "U7") (pin "42") (pinfunction "PB6_42") (pintype "bidirectional+no_connect"))
    )
    (net (code "33") (name "/SDA") (class "Default")
      (node (ref "U7") (pin "43") (pinfunction "PB7_43") (pintype "bidirectional+no_connect"))
    )
    (net (code "34") (name "/SPDLED") (class "Default")
      (node (ref "LED2") (pin "2") (pinfunction "2_2") (pintype "passive"))
      (node (ref "U4") (pin "24") (pinfunction "SPDLED_24") (pintype "passive"))
    )
    (net (code "35") (name "/SWCLK") (class "Default")
      (node (ref "P1") (pin "3") (pinfunction "SWCLK_3") (pintype "passive"))
      (node (ref "U7") (pin "37") (pinfunction "PA14/JTCK/SWCLK_37") (pintype "bidirectional"))
    )
    (net (code "36") (name "/SWDIO") (class "Default")
      (node (ref "P1") (pin "2") (pinfunction "SWDIO_2") (pintype "passive"))
      (node (ref "U7") (pin "34") (pinfunction "PA13/JTMS/SWDIO_34") (pintype "bidirectional"))
    )
    (net (code "37") (name "/TX1") (class "Default")
      (node (ref "R37") (pin "1") (pinfunction "1_1") (pintype "passive"))
      (node (ref "U1") (pin "4") (pinfunction "DI_4") (pintype "passive"))
      (node (ref "U7") (pin "30") (pinfunction "PA9_30") (pintype "bidirectional"))
      (node (ref "U8") (pin "3") (pinfunction "RXD_3") (pintype "passive"))
    )
    (net (code "38") (name "/TX2") (class "Default")
      (node (ref "CN1") (pin "4") (pinfunction "4_4") (pintype "passive"))
      (node (ref "U7") (pin "12") (pinfunction "PA2_12") (pintype "passive"))
    )
    (net (code "39") (name "/TX3") (class "Default")
      (node (ref "R38") (pin "1") (pinfunction "1_1") (pintype "passive"))
      (node (ref "U2") (pin "4") (pinfunction "DI_4") (pintype "passive"))
      (node (ref "U7") (pin "21") (pinfunction "PB10_21") (pintype "bidirectional"))
    )
    (net (code "40") (name "/TXN") (class "Default")
      (node (ref "R20") (pin "2") (pinfunction "2_2") (pintype "passive"))
      (node (ref "RJ1") (pin "4") (pinfunction "TD-_4") (pintype "passive"))
      (node (ref "U4") (pin "1") (pinfunction "TXN_1") (pintype "passive"))
    )
    (net (code "41") (name "/TXP") (class "Default")
      (node (ref "R19") (pin "2") (pinfunction "2_2") (pintype "passive"))
      (node (ref "RJ1") (pin "3") (pinfunction "TD+_3") (pintype "passive"))
      (node (ref "U4") (pin "2") (pinfunction "TXP_2") (pintype "passive"))
    )
    (net (code "42") (name "/W5500_INTn") (class "Default")
      (node (ref "R23") (pin "2") (pinfunction "2_2") (pintype "passive"))
      (node (ref "U4") (pin "36") (pinfunction "INTn_36") (pintype "passive"))
      (node (ref "U7") (pin "46") (pinfunction "PB9_46") (pintype "bidirectional"))
    )
    (net (code "43") (name "/W5500_MISO") (class "Default")
      (node (ref "U4") (pin "34") (pinfunction "MISO_34") (pintype "passive"))
      (node (ref "U7") (pin "27") (pinfunction "PB14_27") (pintype "bidirectional"))
    )
    (net (code "44") (name "/W5500_MOSI") (class "Default")
      (node (ref "U4") (pin "35") (pinfunction "MOSI_35") (pintype "passive"))
      (node (ref "U7") (pin "28") (pinfunction "PB15_28") (pintype "bidirectional"))
    )
    (net (code "45") (name "/W5500_RST") (class "Default")
      (node (ref "R22") (pin "2") (pinfunction "2_2") (pintype "passive"))
      (node (ref "U4") (pin "37") (pinfunction "RSTn_37") (pintype "passive"))
      (node (ref "U7") (pin "45") (pinfunction "PB8_45") (pintype "bidirectional"))
    )
    (net (code "46") (name "/W5500_SCLK") (class "Default")
      (node (ref "U4") (pin "33") (pinfunction "SCLK_33") (pintype "passive"))
      (node (ref "U7") (pin "26") (pinfunction "PB13_26") (pintype "bidirectional"))
    )
    (net (code "47") (name "/W5500_SCSn") (class "Default")
      (node (ref "U4") (pin "32") (pinfunction "SCSn_32") (pintype "passive"))
      (node (ref "U7") (pin "25") (pinfunction "PB12_25") (pintype "bidirectional"))
    )
    (net (code "48") (name "/W5500_XI") (class "Default")
      (node (ref "C17") (pin "1") (pinfunction "1_1") (pintype "passive"))
      (node (ref "U4") (pin "31") (pinfunction "XO_31") (pintype "passive"))
      (node (ref "X1") (pin "1") (pinfunction "OSC1_1") (pintype "passive"))
    )
    (net (code "49") (name "/W5500_XO") (class "Default")
      (node (ref "C2") (pin "2") (pinfunction "2_2") (pintype "passive"))
      (node (ref "U4") (pin "30") (pinfunction "XI/CLKIN_30") (pintype "passive"))
      (node (ref "X1") (pin "3") (pinfunction "OSC2_3") (pintype "passive"))
    )
    (net (code "50") (name "AGND") (class "Default")
      (node (ref "C10") (pin "2") (pinfunction "2_2") (pintype "passive"))
      (node (ref "C13") (pin "2") (pinfunction "2_2") (pintype "passive"))
      (node (ref "C14") (pin "2") (pinfunction "2_2") (pintype "passive"))
      (node (ref "C15") (pin "2") (pinfunction "2_2") (pintype "passive"))
      (node (ref "C16") (pin "2") (pinfunction "2_2") (pintype "passive"))
      (node (ref "C17") (pin "2") (pinfunction "2_2") (pintype "passive"))
      (node (ref "C18") (pin "2") (pinfunction "2_2") (pintype "passive"))
      (node (ref "C2") (pin "1") (pinfunction "1_1") (pintype "passive"))
      (node (ref "C9") (pin "1") (pinfunction "1_1") (pintype "passive"))
      (node (ref "R13") (pin "1") (pinfunction "1_1") (pintype "passive"))
      (node (ref "R14") (pin "1") (pinfunction "1_1") (pintype "passive"))
      (node (ref "R15") (pin "1") (pinfunction "1_1") (pintype "passive"))
      (node (ref "R16") (pin "2") (pinfunction "2_2") (pintype "passive"))
      (node (ref "R17") (pin "1") (pinfunction "1_1") (pintype "passive"))
      (node (ref "R18") (pin "1") (pinfunction "1_1") (pintype "passive"))
      (node (ref "R29") (pin "1") (pinfunction "1_1") (pintype "passive"))
      (node (ref "R45") (pin "1") (pinfunction "1_1") (pintype "passive"))
      (node (ref "U4") (pin "14") (pinfunction "AGND_14") (pintype "passive"))
      (node (ref "U4") (pin "16") (pinfunction "AGND_16") (pintype "passive"))
      (node (ref "U4") (pin "19") (pinfunction "AGND_19") (pintype "passive"))
      (node (ref "U4") (pin "23") (pinfunction "RSVD_23") (pintype "passive"))
      (node (ref "U4") (pin "29") (pinfunction "GND_29") (pintype "passive"))
      (node (ref "U4") (pin "3") (pinfunction "AGND_3") (pintype "passive"))
      (node (ref "U4") (pin "48") (pinfunction "AGND_48") (pintype "passive"))
      (node (ref "U4") (pin "9") (pinfunction "AGND_9") (pintype "passive"))
      (node (ref "X1") (pin "2") (pinfunction "GND_2") (pintype "passive"))
      (node (ref "X1") (pin "4") (pinfunction "GND_4") (pintype "passive"))
    )
    (net (code "51") (name "GND") (class "Default")
      (node (ref "C1") (pin "2") (pinfunction "2_2") (pintype "passive"))
      (node (ref "C19") (pin "2") (pinfunction "2_2") (pintype "passive"))
      (node (ref "C20") (pin "2") (pinfunction "2_2") (pintype "passive"))
      (node (ref "C21") (pin "2") (pinfunction "2_2") (pintype "passive"))
      (node (ref "C22") (pin "2") (pinfunction "2_2") (pintype "passive"))
      (node (ref "C23") (pin "2") (pinfunction "2_2") (pintype "passive"))
      (node (ref "C26") (pin "1") (pinfunction "1_1") (pintype "passive"))
      (node (ref "C27") (pin "1") (pinfunction "1_1") (pintype "passive"))
      (node (ref "C28") (pin "1") (pinfunction "1_1") (pintype "passive"))
      (node (ref "C29") (pin "1") (pinfunction "1_1") (pintype "passive"))
      (node (ref "C3") (pin "2") (pinfunction "2_2") (pintype "passive"))
      (node (ref "C31") (pin "1") (pinfunction "1_1") (pintype "passive"))
      (node (ref "C32") (pin "1") (pinfunction "1_1") (pintype "passive"))
      (node (ref "C33") (pin "1") (pinfunction "1_1") (pintype "passive"))
      (node (ref "C34") (pin "2") (pinfunction "2_2") (pintype "passive"))
      (node (ref "C35") (pin "2") (pinfunction "2_2") (pintype "passive"))
      (node (ref "C36") (pin "2") (pinfunction "2_2") (pintype "passive"))
      (node (ref "C37") (pin "2") (pinfunction "2_2") (pintype "passive"))
      (node (ref "C38") (pin "2") (pinfunction "2_2") (pintype "passive"))
      (node (ref "C39") (pin "2") (pinfunction "2_2") (pintype "passive"))
      (node (ref "C4") (pin "2") (pinfunction "2_2") (pintype "passive"))
      (node (ref "C40") (pin "2") (pinfunction "2_2") (pintype "passive"))
      (node (ref "C5") (pin "2") (pinfunction "2_2") (pintype "passive"))
      (node (ref "C6") (pin "2") (pinfunction "2_2") (pintype "passive"))
      (node (ref "C7") (pin "2") (pinfunction "2_2") (pintype "passive"))
      (node (ref "C8") (pin "2") (pinfunction "2_2") (pintype "passive"))
      (node (ref "CN1") (pin "2") (pinfunction "2_2") (pintype "passive"))
      (node (ref "CN2") (pin "4") (pinfunction "GND_4") (pintype "passive"))
      (node (ref "CN5") (pin "2") (pinfunction "GND_2") (pintype "passive"))
      (node (ref "D1") (pin "3") (pinfunction "3_3") (pintype "passive"))
      (node (ref "D2") (pin "3") (pinfunction "3_3") (pintype "passive"))
      (node (ref "D3") (pin "2") (pinfunction "A_2") (pintype "passive"))
      (node (ref "K1") (pin "1") (pinfunction "1_1") (pintype "passive"))
      (node (ref "P1") (pin "4") (pinfunction "GND_4") (pintype "passive"))
      (node (ref "P1") (pin "5") (pinfunction "GND_5") (pintype "passive"))
      (node (ref "P2") (pin "2") (pinfunction "2_2") (pintype "passive"))
      (node (ref "Q1") (pin "2") (pinfunction "E_2") (pintype "passive"))
      (node (ref "Q2") (pin "2") (pinfunction "E_2") (pintype "passive"))
      (node (ref "R33") (pin "2") (pinfunction "2_2") (pintype "passive"))
      (node (ref "R40") (pin "2") (pinfunction "2_2") (pintype "passive"))
      (node (ref "R41") (pin "2") (pinfunction "2_2") (pintype "passive"))
      (node (ref "R45") (pin "2") (pinfunction "2_2") (pintype "passive"))
      (node (ref "R5") (pin "1") (pinfunction "1_1") (pintype "passive"))
      (node (ref "R8") (pin "1") (pinfunction "1_1") (pintype "passive"))
      (node (ref "U1") (pin "5") (pinfunction "GND_5") (pintype "passive"))
      (node (ref "U2") (pin "5") (pinfunction "GND_5") (pintype "passive"))
      (node (ref "U3") (pin "4") (pinfunction "GND_4") (pintype "passive"))
      (node (ref "U5") (pin "3") (pinfunction "GND_3") (pintype "passive"))
      (node (ref "U5") (pin "5") (pinfunction "ON/OFF_5") (pintype "passive"))
      (node (ref "U5") (pin "6") (pinfunction "EP_6") (pintype "passive"))
      (node (ref "U6") (pin "1") (pinfunction "GND/ADJ_1") (pintype "passive"))
      (node (ref "U7") (pin "23") (pinfunction "VSS_1_23") (pintype "power_in"))
      (node (ref "U7") (pin "35") (pinfunction "VSS_2_35") (pintype "power_in"))
      (node (ref "U7") (pin "47") (pinfunction "VSS_3_47") (pintype "power_in"))
      (node (ref "U7") (pin "8") (pinfunction "VSSA_8") (pintype "power_in"))
      (node (ref "U8") (pin "1") (pinfunction "GND_1") (pintype "passive"))
      (node (ref "USB1") (pin "A1B12") (pinfunction "GND_A1B12") (pintype "passive"))
      (node (ref "USB1") (pin "B1A12") (pinfunction "GND_B1A12") (pintype "passive"))
    )
    (net (code "52") (name "Net-(C24-Pad1)") (class "Default")
      (node (ref "C24") (pin "1") (pinfunction "1_1") (pintype "passive"))
      (node (ref "C25") (pin "1") (pinfunction "1_1") (pintype "passive"))
    )
    (net (code "53") (name "Net-(D3-C)") (class "Default")
      (node (ref "D3") (pin "1") (pinfunction "C_1") (pintype "passive"))
      (node (ref "L1") (pin "2") (pinfunction "2_2") (pintype "passive"))
      (node (ref "U5") (pin "2") (pinfunction "OUTPUT_2") (pintype "passive"))
    )
    (net (code "54") (name "Net-(LED1-Pad1)") (class "Default")
      (node (ref "LED1") (pin "1") (pinfunction "1_1") (pintype "passive"))
      (node (ref "R28") (pin "1") (pinfunction "1_1") (pintype "passive"))
    )
    (net (code "55") (name "Net-(LED2-Pad1)") (class "Default")
      (node (ref "LED2") (pin "1") (pinfunction "1_1") (pintype "passive"))
      (node (ref "R30") (pin "1") (pinfunction "1_1") (pintype "passive"))
    )
    (net (code "56") (name "Net-(LED3-Pad1)") (class "Default")
      (node (ref "LED3") (pin "1") (pinfunction "1_1") (pintype "passive"))
      (node (ref "R31") (pin "1") (pinfunction "1_1") (pintype "passive"))
    )
    (net (code "57") (name "Net-(LED4-Pad1)") (class "Default")
      (node (ref "LED4") (pin "1") (pinfunction "1_1") (pintype "passive"))
      (node (ref "R11") (pin "1") (pinfunction "1_1") (pintype "passive"))
    )
    (net (code "58") (name "Net-(Q1-B)") (class "Default")
      (node (ref "Q1") (pin "1") (pinfunction "B_1") (pintype "passive"))
      (node (ref "R37") (pin "2") (pinfunction "2_2") (pintype "passive"))
      (node (ref "R40") (pin "1") (pinfunction "1_1") (pintype "passive"))
    )
    (net (code "59") (name "Net-(Q1-C)") (class "Default")
      (node (ref "Q1") (pin "3") (pinfunction "C_3") (pintype "passive"))
      (node (ref "R35") (pin "2") (pinfunction "2_2") (pintype "passive"))
      (node (ref "U1") (pin "2") (pinfunction "RE#_2") (pintype "passive"))
      (node (ref "U1") (pin "3") (pinfunction "DE_3") (pintype "passive"))
    )
    (net (code "60") (name "Net-(Q2-B)") (class "Default")
      (node (ref "Q2") (pin "1") (pinfunction "B_1") (pintype "passive"))
      (node (ref "R38") (pin "2") (pinfunction "2_2") (pintype "passive"))
      (node (ref "R41") (pin "1") (pinfunction "1_1") (pintype "passive"))
    )
    (net (code "61") (name "Net-(Q2-C)") (class "Default")
      (node (ref "Q2") (pin "3") (pinfunction "C_3") (pintype "passive"))
      (node (ref "R36") (pin "2") (pinfunction "2_2") (pintype "passive"))
      (node (ref "U2") (pin "2") (pinfunction "RE#_2") (pintype "passive"))
      (node (ref "U2") (pin "3") (pinfunction "DE_3") (pintype "passive"))
    )
    (net (code "62") (name "Net-(Q3-B)") (class "Default")
      (node (ref "Q3") (pin "1") (pinfunction "B_1") (pintype "passive"))
      (node (ref "R42") (pin "2") (pinfunction "2_2") (pintype "passive"))
    )
    (net (code "63") (name "Net-(Q3-C)") (class "Default")
      (node (ref "D4") (pin "1") (pinfunction "1_1") (pintype "passive"))
      (node (ref "Q3") (pin "3") (pinfunction "C_3") (pintype "passive"))
      (node (ref "R39") (pin "2") (pinfunction "2_2") (pintype "passive"))
    )
    (net (code "64") (name "Net-(Q3-E)") (class "Default")
      (node (ref "Q3") (pin "2") (pinfunction "E_2") (pintype "passive"))
      (node (ref "R43") (pin "1") (pinfunction "1_1") (pintype "passive"))
      (node (ref "U8") (pin "14") (pinfunction "RTS#_14") (pintype "passive"))
    )
    (net (code "65") (name "Net-(Q4-B)") (class "Default")
      (node (ref "Q4") (pin "1") (pinfunction "B_1") (pintype "passive"))
      (node (ref "R43") (pin "2") (pinfunction "2_2") (pintype "passive"))
    )
    (net (code "66") (name "Net-(Q4-C)") (class "Default")
      (node (ref "Q4") (pin "3") (pinfunction "C_3") (pintype "passive"))
      (node (ref "R44") (pin "2") (pinfunction "2_2") (pintype "passive"))
    )
    (net (code "67") (name "Net-(R13-Pad2)") (class "Default")
      (node (ref "R13") (pin "2") (pinfunction "2_2") (pintype "passive"))
      (node (ref "U4") (pin "42") (pinfunction "RSVD_42") (pintype "passive"))
    )
    (net (code "68") (name "Net-(R14-Pad2)") (class "Default")
      (node (ref "R14") (pin "2") (pinfunction "2_2") (pintype "passive"))
      (node (ref "U4") (pin "41") (pinfunction "RSVD_41") (pintype "passive"))
    )
    (net (code "69") (name "Net-(R15-Pad2)") (class "Default")
      (node (ref "R15") (pin "2") (pinfunction "2_2") (pintype "passive"))
      (node (ref "U4") (pin "40") (pinfunction "RSVD_40") (pintype "passive"))
    )
    (net (code "70") (name "Net-(R17-Pad2)") (class "Default")
      (node (ref "R17") (pin "2") (pinfunction "2_2") (pintype "passive"))
      (node (ref "U4") (pin "39") (pinfunction "RSVD_39") (pintype "passive"))
    )
    (net (code "71") (name "Net-(R18-Pad2)") (class "Default")
      (node (ref "R18") (pin "2") (pinfunction "2_2") (pintype "passive"))
      (node (ref "U4") (pin "38") (pinfunction "RSVD_38") (pintype "passive"))
    )
    (net (code "72") (name "Net-(RJ1-CHS_GND)") (class "Default")
      (node (ref "C18") (pin "1") (pinfunction "1_1") (pintype "passive"))
      (node (ref "R29") (pin "2") (pinfunction "2_2") (pintype "passive"))
      (node (ref "RJ1") (pin "10") (pinfunction "CHS_GND_10") (pintype "passive"))
      (node (ref "RJ1") (pin "13") (pinfunction "13_13") (pintype "passive"))
      (node (ref "RJ1") (pin "14") (pinfunction "14_14") (pintype "passive"))
    )
    (net (code "73") (name "Net-(RJ1-CT_RX)") (class "Default")
      (node (ref "C25") (pin "2") (pinfunction "2_2") (pintype "passive"))
      (node (ref "R26") (pin "2") (pinfunction "2_2") (pintype "passive"))
      (node (ref "R27") (pin "2") (pinfunction "2_2") (pintype "passive"))
      (node (ref "RJ1") (pin "6") (pinfunction "CT_RX_6") (pintype "passive"))
    )
    (net (code "74") (name "Net-(RJ1-CT_TX)") (class "Default")
      (node (ref "C24") (pin "2") (pinfunction "2_2") (pintype "passive"))
      (node (ref "R21") (pin "2") (pinfunction "2_2") (pintype "passive"))
      (node (ref "RJ1") (pin "5") (pinfunction "CT_TX_5") (pintype "passive"))
    )
    (net (code "75") (name "Net-(RJ1-LED+)") (class "Default")
      (node (ref "R25") (pin "2") (pinfunction "2_2") (pintype "passive"))
      (node (ref "RJ1") (pin "12") (pinfunction "LED+_12") (pintype "passive"))
    )
    (net (code "76") (name "Net-(RJ1-LED1+)") (class "Default")
      (node (ref "R24") (pin "2") (pinfunction "2_2") (pintype "passive"))
      (node (ref "RJ1") (pin "1") (pinfunction "LED1+_1") (pintype "passive"))
    )
    (net (code "77") (name "Net-(RJ1-RD+)") (class "Default")
      (node (ref "C11") (pin "2") (pinfunction "2_2") (pintype "passive"))
      (node (ref "RJ1") (pin "7") (pinfunction "RD+_7") (pintype "passive"))
    )
    (net (code "78") (name "Net-(RJ1-RD-)") (class "Default")
      (node (ref "C12") (pin "2") (pinfunction "2_2") (pintype "passive"))
      (node (ref "RJ1") (pin "8") (pinfunction "RD-_8") (pintype "passive"))
    )
    (net (code "79") (name "Net-(U4-1V2O)") (class "Default")
      (node (ref "C9") (pin "2") (pinfunction "2_2") (pintype "passive"))
      (node (ref "U4") (pin "22") (pinfunction "1V2O_22") (pintype "passive"))
    )
    (net (code "80") (name "Net-(U4-EXRES1)") (class "Default")
      (node (ref "R16") (pin "1") (pinfunction "1_1") (pintype "passive"))
      (node (ref "U4") (pin "10") (pinfunction "EXRES1_10") (pintype "passive"))
    )
    (net (code "81") (name "Net-(U4-TOCAP)") (class "Default")
      (node (ref "C10") (pin "1") (pinfunction "1_1") (pintype "passive"))
      (node (ref "U4") (pin "20") (pinfunction "TOCAP_20") (pintype "passive"))
    )
    (net (code "82") (name "Net-(U8-DTR#)") (class "Default")
      (node (ref "R42") (pin "1") (pinfunction "1_1") (pintype "passive"))
      (node (ref "U8") (pin "13") (pinfunction "DTR#_13") (pintype "passive"))
    )
    (net (code "83") (name "Net-(U8-V3)") (class "Default")
      (node (ref "C36") (pin "1") (pinfunction "1_1") (pintype "passive"))
      (node (ref "U8") (pin "4") (pinfunction "V3_4") (pintype "passive"))
    )
    (net (code "84") (name "Net-(U8-XI)") (class "Default")
      (node (ref "C37") (pin "1") (pinfunction "1_1") (pintype "passive"))
      (node (ref "U8") (pin "7") (pinfunction "XI_7") (pintype "passive"))
      (node (ref "Y2") (pin "2") (pinfunction "2_2") (pintype "passive"))
    )
    (net (code "85") (name "Net-(U8-XO)") (class "Default")
      (node (ref "C38") (pin "1") (pinfunction "1_1") (pintype "passive"))
      (node (ref "U8") (pin "8") (pinfunction "XO_8") (pintype "passive"))
      (node (ref "Y2") (pin "1") (pinfunction "1_1") (pintype "passive"))
    )
    (net (code "86") (name "VCCA_3.3V") (class "Default")
      (node (ref "C13") (pin "1") (pinfunction "1_1") (pintype "passive"))
      (node (ref "C14") (pin "1") (pinfunction "1_1") (pintype "passive"))
      (node (ref "C15") (pin "1") (pinfunction "1_1") (pintype "passive"))
      (node (ref "C16") (pin "1") (pinfunction "1_1") (pintype "passive"))
      (node (ref "C39") (pin "1") (pinfunction "1_1") (pintype "passive"))
      (node (ref "C40") (pin "1") (pinfunction "1_1") (pintype "passive"))
      (node (ref "L2") (pin "2") (pinfunction "2_2") (pintype "passive"))
      (node (ref "R10") (pin "1") (pinfunction "1_1") (pintype "passive"))
      (node (ref "R12") (pin "1") (pinfunction "1_1") (pintype "passive"))
      (node (ref "R19") (pin "1") (pinfunction "1_1") (pintype "passive"))
      (node (ref "R20") (pin "1") (pinfunction "1_1") (pintype "passive"))
      (node (ref "R21") (pin "1") (pinfunction "1_1") (pintype "passive"))
      (node (ref "R22") (pin "1") (pinfunction "1_1") (pintype "passive"))
      (node (ref "R23") (pin "1") (pinfunction "1_1") (pintype "passive"))
      (node (ref "R24") (pin "1") (pinfunction "1_1") (pintype "passive"))
      (node (ref "R25") (pin "1") (pinfunction "1_1") (pintype "passive"))
      (node (ref "R9") (pin "1") (pinfunction "1_1") (pintype "passive"))
      (node (ref "U4") (pin "11") (pinfunction "AVDD_11") (pintype "passive"))
      (node (ref "U4") (pin "15") (pinfunction "AVDD_15") (pintype "passive"))
      (node (ref "U4") (pin "17") (pinfunction "AVDD_17") (pintype "passive"))
      (node (ref "U4") (pin "21") (pinfunction "AVDD_21") (pintype "passive"))
      (node (ref "U4") (pin "28") (pinfunction "VDD_28") (pintype "passive"))
      (node (ref "U4") (pin "4") (pinfunction "AVDD_4") (pintype "passive"))
      (node (ref "U4") (pin "8") (pinfunction "AVDD_8") (pintype "passive"))
    )
    (net (code "87") (name "unconnected-(CN1-Pad7)") (class "Default")
      (node (ref "CN1") (pin "7") (pinfunction "7_7") (pintype "passive"))
    )
    (net (code "88") (name "unconnected-(CN1-Pad8)") (class "Default")
      (node (ref "CN1") (pin "8") (pinfunction "8_8") (pintype "passive"))
    )
    (net (code "89") (name "unconnected-(CN2-NC-Pad5)") (class "Default")
      (node (ref "CN2") (pin "5") (pinfunction "NC_5") (pintype "passive"))
    )
    (net (code "90") (name "unconnected-(CN2-NC-Pad6)") (class "Default")
      (node (ref "CN2") (pin "6") (pinfunction "NC_6") (pintype "passive"))
    )
    (net (code "91") (name "unconnected-(RJ1-NC-Pad9)") (class "Default")
      (node (ref "RJ1") (pin "9") (pinfunction "NC_9") (pintype "passive+no_connect"))
    )
    (net (code "92") (name "unconnected-(U3-NC-Pad3)") (class "Default")
      (node (ref "U3") (pin "3") (pinfunction "NC_3") (pintype "passive"))
    )
    (net (code "93") (name "unconnected-(U4-DNC-Pad7)") (class "Default")
      (node (ref "U4") (pin "7") (pinfunction "DNC_7") (pintype "passive+no_connect"))
    )
    (net (code "94") (name "unconnected-(U4-NC-Pad12)") (class "Default")
      (node (ref "U4") (pin "12") (pinfunction "NC_12") (pintype "passive+no_connect"))
    )
    (net (code "95") (name "unconnected-(U4-NC-Pad13)") (class "Default")
      (node (ref "U4") (pin "13") (pinfunction "NC_13") (pintype "passive+no_connect"))
    )
    (net (code "96") (name "unconnected-(U4-NC-Pad46)") (class "Default")
      (node (ref "U4") (pin "46") (pinfunction "NC_46") (pintype "passive+no_connect"))
    )
    (net (code "97") (name "unconnected-(U4-NC-Pad47)") (class "Default")
      (node (ref "U4") (pin "47") (pinfunction "NC_47") (pintype "passive+no_connect"))
    )
    (net (code "98") (name "unconnected-(U4-VBG-Pad18)") (class "Default")
      (node (ref "U4") (pin "18") (pinfunction "VBG_18") (pintype "passive+no_connect"))
    )
    (net (code "99") (name "unconnected-(U7-PA7-Pad17)") (class "Default")
      (node (ref "U7") (pin "17") (pinfunction "PA7_17") (pintype "passive"))
    )
    (net (code "100") (name "unconnected-(U7-PA8-Pad29)") (class "Default")
      (node (ref "U7") (pin "29") (pinfunction "PA8_29") (pintype "bidirectional"))
    )
    (net (code "101") (name "unconnected-(U7-PA11-Pad32)") (class "Default")
      (node (ref "U7") (pin "32") (pinfunction "PA11_32") (pintype "bidirectional"))
    )
    (net (code "102") (name "unconnected-(U7-PA12-Pad33)") (class "Default")
      (node (ref "U7") (pin "33") (pinfunction "PA12_33") (pintype "bidirectional"))
    )
    (net (code "103") (name "unconnected-(U7-PA15{slash}JTDI-Pad38)") (class "Default")
      (node (ref "U7") (pin "38") (pinfunction "PA15/JTDI_38") (pintype "bidirectional"))
    )
    (net (code "104") (name "unconnected-(U7-PB0-Pad18)") (class "Default")
      (node (ref "U7") (pin "18") (pinfunction "PB0_18") (pintype "bidirectional"))
    )
    (net (code "105") (name "unconnected-(U7-PB1-Pad19)") (class "Default")
      (node (ref "U7") (pin "19") (pinfunction "PB1_19") (pintype "bidirectional"))
    )
    (net (code "106") (name "unconnected-(U7-PB2{slash}BOOT1-Pad20)") (class "Default")
      (node (ref "U7") (pin "20") (pinfunction "PB2/BOOT1_20") (pintype "bidirectional"))
    )
    (net (code "107") (name "unconnected-(U7-PB3{slash}JTDO-Pad39)") (class "Default")
      (node (ref "U7") (pin "39") (pinfunction "PB3/JTDO_39") (pintype "bidirectional"))
    )
    (net (code "108") (name "unconnected-(U7-PC13-TAMPER-RTC-Pad2)") (class "Default")
      (node (ref "U7") (pin "2") (pinfunction "PC13-TAMPER-RTC_2") (pintype "bidirectional"))
    )
    (net (code "109") (name "unconnected-(U7-PC14-OSC32_IN-Pad3)") (class "Default")
      (node (ref "U7") (pin "3") (pinfunction "PC14-OSC32_IN_3") (pintype "bidirectional"))
    )
    (net (code "110") (name "unconnected-(U7-PC15-OSC32_OUT-Pad4)") (class "Default")
      (node (ref "U7") (pin "4") (pinfunction "PC15-OSC32_OUT_4") (pintype "bidirectional"))
    )
    (net (code "111") (name "unconnected-(U8-CTS#-Pad9)") (class "Default")
      (node (ref "U8") (pin "9") (pinfunction "CTS#_9") (pintype "passive"))
    )
    (net (code "112") (name "unconnected-(U8-DCD#-Pad12)") (class "Default")
      (node (ref "U8") (pin "12") (pinfunction "DCD#_12") (pintype "passive"))
    )
    (net (code "113") (name "unconnected-(U8-DSR#-Pad10)") (class "Default")
      (node (ref "U8") (pin "10") (pinfunction "DSR#_10") (pintype "passive"))
    )
    (net (code "114") (name "unconnected-(U8-R232-Pad15)") (class "Default")
      (node (ref "U8") (pin "15") (pinfunction "R232_15") (pintype "passive"))
    )
    (net (code "115") (name "unconnected-(U8-RI#-Pad11)") (class "Default")
      (node (ref "U8") (pin "11") (pinfunction "RI#_11") (pintype "passive"))
    )
    (net (code "116") (name "unconnected-(USB1-CC1-PadA5)") (class "Default")
      (node (ref "USB1") (pin "A5") (pinfunction "CC1_A5") (pintype "passive"))
    )
    (net (code "117") (name "unconnected-(USB1-CC2-PadB5)") (class "Default")
      (node (ref "USB1") (pin "B5") (pinfunction "CC2_B5") (pintype "passive"))
    )
    (net (code "118") (name "unconnected-(USB1-Pad12)") (class "Default")
      (node (ref "USB1") (pin "12") (pinfunction "12_12") (pintype "passive"))
    )
    (net (code "119") (name "unconnected-(USB1-Pad13)") (class "Default")
      (node (ref "USB1") (pin "13") (pinfunction "13_13") (pintype "passive"))
    )
    (net (code "120") (name "unconnected-(USB1-Pad14)") (class "Default")
      (node (ref "USB1") (pin "14") (pinfunction "14_14") (pintype "passive"))
    )
    (net (code "121") (name "unconnected-(USB1-Pad15)") (class "Default")
      (node (ref "USB1") (pin "15") (pinfunction "15_15") (pintype "passive"))
    )
    (net (code "122") (name "unconnected-(USB1-SBU1-PadA8)") (class "Default")
      (node (ref "USB1") (pin "A8") (pinfunction "SBU1_A8") (pintype "passive"))
    )
    (net (code "123") (name "unconnected-(USB1-SBU2-PadB8)") (class "Default")
      (node (ref "USB1") (pin "B8") (pinfunction "SBU2_B8") (pintype "passive"))
    )
  )
)
